# Sheet1.net
KiCad netlist of a schematic drawn in Altium Designer
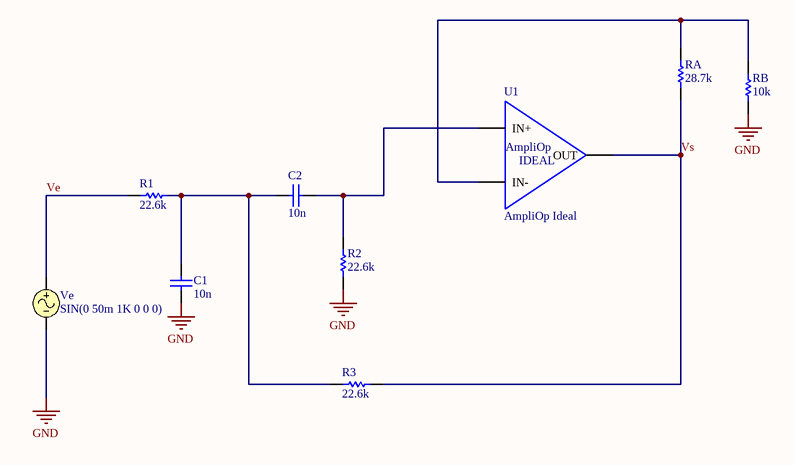
[diagram p0: Sheet1.SchDoc]

(export (version "E")
  (design (tool "Eeschema 10.0.6"))
  (components
    (comp (ref "C1")
      (value "10n")
      (description "Capacitor")
      (libsource (lib "Simulation Generic Components") (part "Capacitor"))
    )
    (comp (ref "C2")
      (value "10n")
      (description "Capacitor")
      (libsource (lib "Simulation Generic Components") (part "Capacitor"))
    )
    (comp (ref "R1")
      (value "22.6k")
      (description "Resistor")
      (libsource (lib "Simulation Generic Components") (part "Resistor"))
    )
    (comp (ref "R2")
      (value "22.6k")
      (description "Resistor")
      (libsource (lib "Simulation Generic Components") (part "Resistor"))
    )
    (comp (ref "R3")
      (value "22.6k")
      (description "Resistor")
      (libsource (lib "Simulation Generic Components") (part "Resistor"))
    )
    (comp (ref "RA")
      (value "28.7k")
      (description "Resistor")
      (libsource (lib "Simulation Generic Components") (part "Resistor"))
    )
    (comp (ref "RB")
      (value "10k")
      (description "Resistor")
      (libsource (lib "Simulation Generic Components") (part "Resistor"))
    )
    (comp (ref "U1") (value "AmpliOp Ideal") (libsource (lib "Composantes_S2") (part "AmpliOp_ideal")))
    (comp (ref "Ve")
      (value "SIN(0 50m 1K 0 0 0)")
      (description "Sinusoidal Voltage Source")
      (fields (field (name "PUBLISHER") "Altium Limited"))
      (libsource (lib "Simulation Sources") (part "VSIN"))
    )
  )
  (nets
    (net (code "1") (name "/Ve") (class "Default")
      (node (ref "R1") (pin "1") (pinfunction "1_1") (pintype "passive"))
      (node (ref "Ve") (pin "1") (pinfunction "1_1") (pintype "passive"))
    )
    (net (code "2") (name "/Vs") (class "Default")
      (node (ref "R3") (pin "2") (pinfunction "2_2") (pintype "passive"))
      (node (ref "RA") (pin "1") (pinfunction "1_1") (pintype "passive"))
      (node (ref "U1") (pin "3") (pinfunction "OUT_3") (pintype "passive"))
    )
    (net (code "3") (name "GND") (class "Default")
      (node (ref "C1") (pin "1") (pinfunction "1_1") (pintype "passive"))
      (node (ref "R2") (pin "1") (pinfunction "1_1") (pintype "passive"))
      (node (ref "RB") (pin "1") (pinfunction "1_1") (pintype "passive"))
      (node (ref "Ve") (pin "2") (pinfunction "2_2") (pintype "passive"))
    )
    (net (code "4") (name "Net-(C1-Pad2)") (class "Default")
      (node (ref "C1") (pin "2") (pinfunction "2_2") (pintype "passive"))
      (node (ref "C2") (pin "1") (pinfunction "1_1") (pintype "passive"))
      (node (ref "R1") (pin "2") (pinfunction "2_2") (pintype "passive"))
      (node (ref "R3") (pin "1") (pinfunction "1_1") (pintype "passive"))
    )
    (net (code "5") (name "Net-(U1-IN+)") (class "Default")
      (node (ref "C2") (pin "2") (pinfunction "2_2") (pintype "passive"))
      (node (ref "R2") (pin "2") (pinfunction "2_2") (pintype "passive"))
      (node (ref "U1") (pin "1") (pinfunction "IN+_1") (pintype "passive"))
    )
    (net (code "6") (name "Net-(U1-IN-)") (class "Default")
      (node (ref "RA") (pin "2") (pinfunction "2_2") (pintype "passive"))
      (node (ref "RB") (pin "2") (pinfunction "2_2") (pintype "passive"))
      (node (ref "U1") (pin "2") (pinfunction "IN-_2") (pintype "passive"))
    )
  )
)
